# Cpcis_connectors_P1_P6.net
KiCad netlist of a schematic drawn in Altium Designer
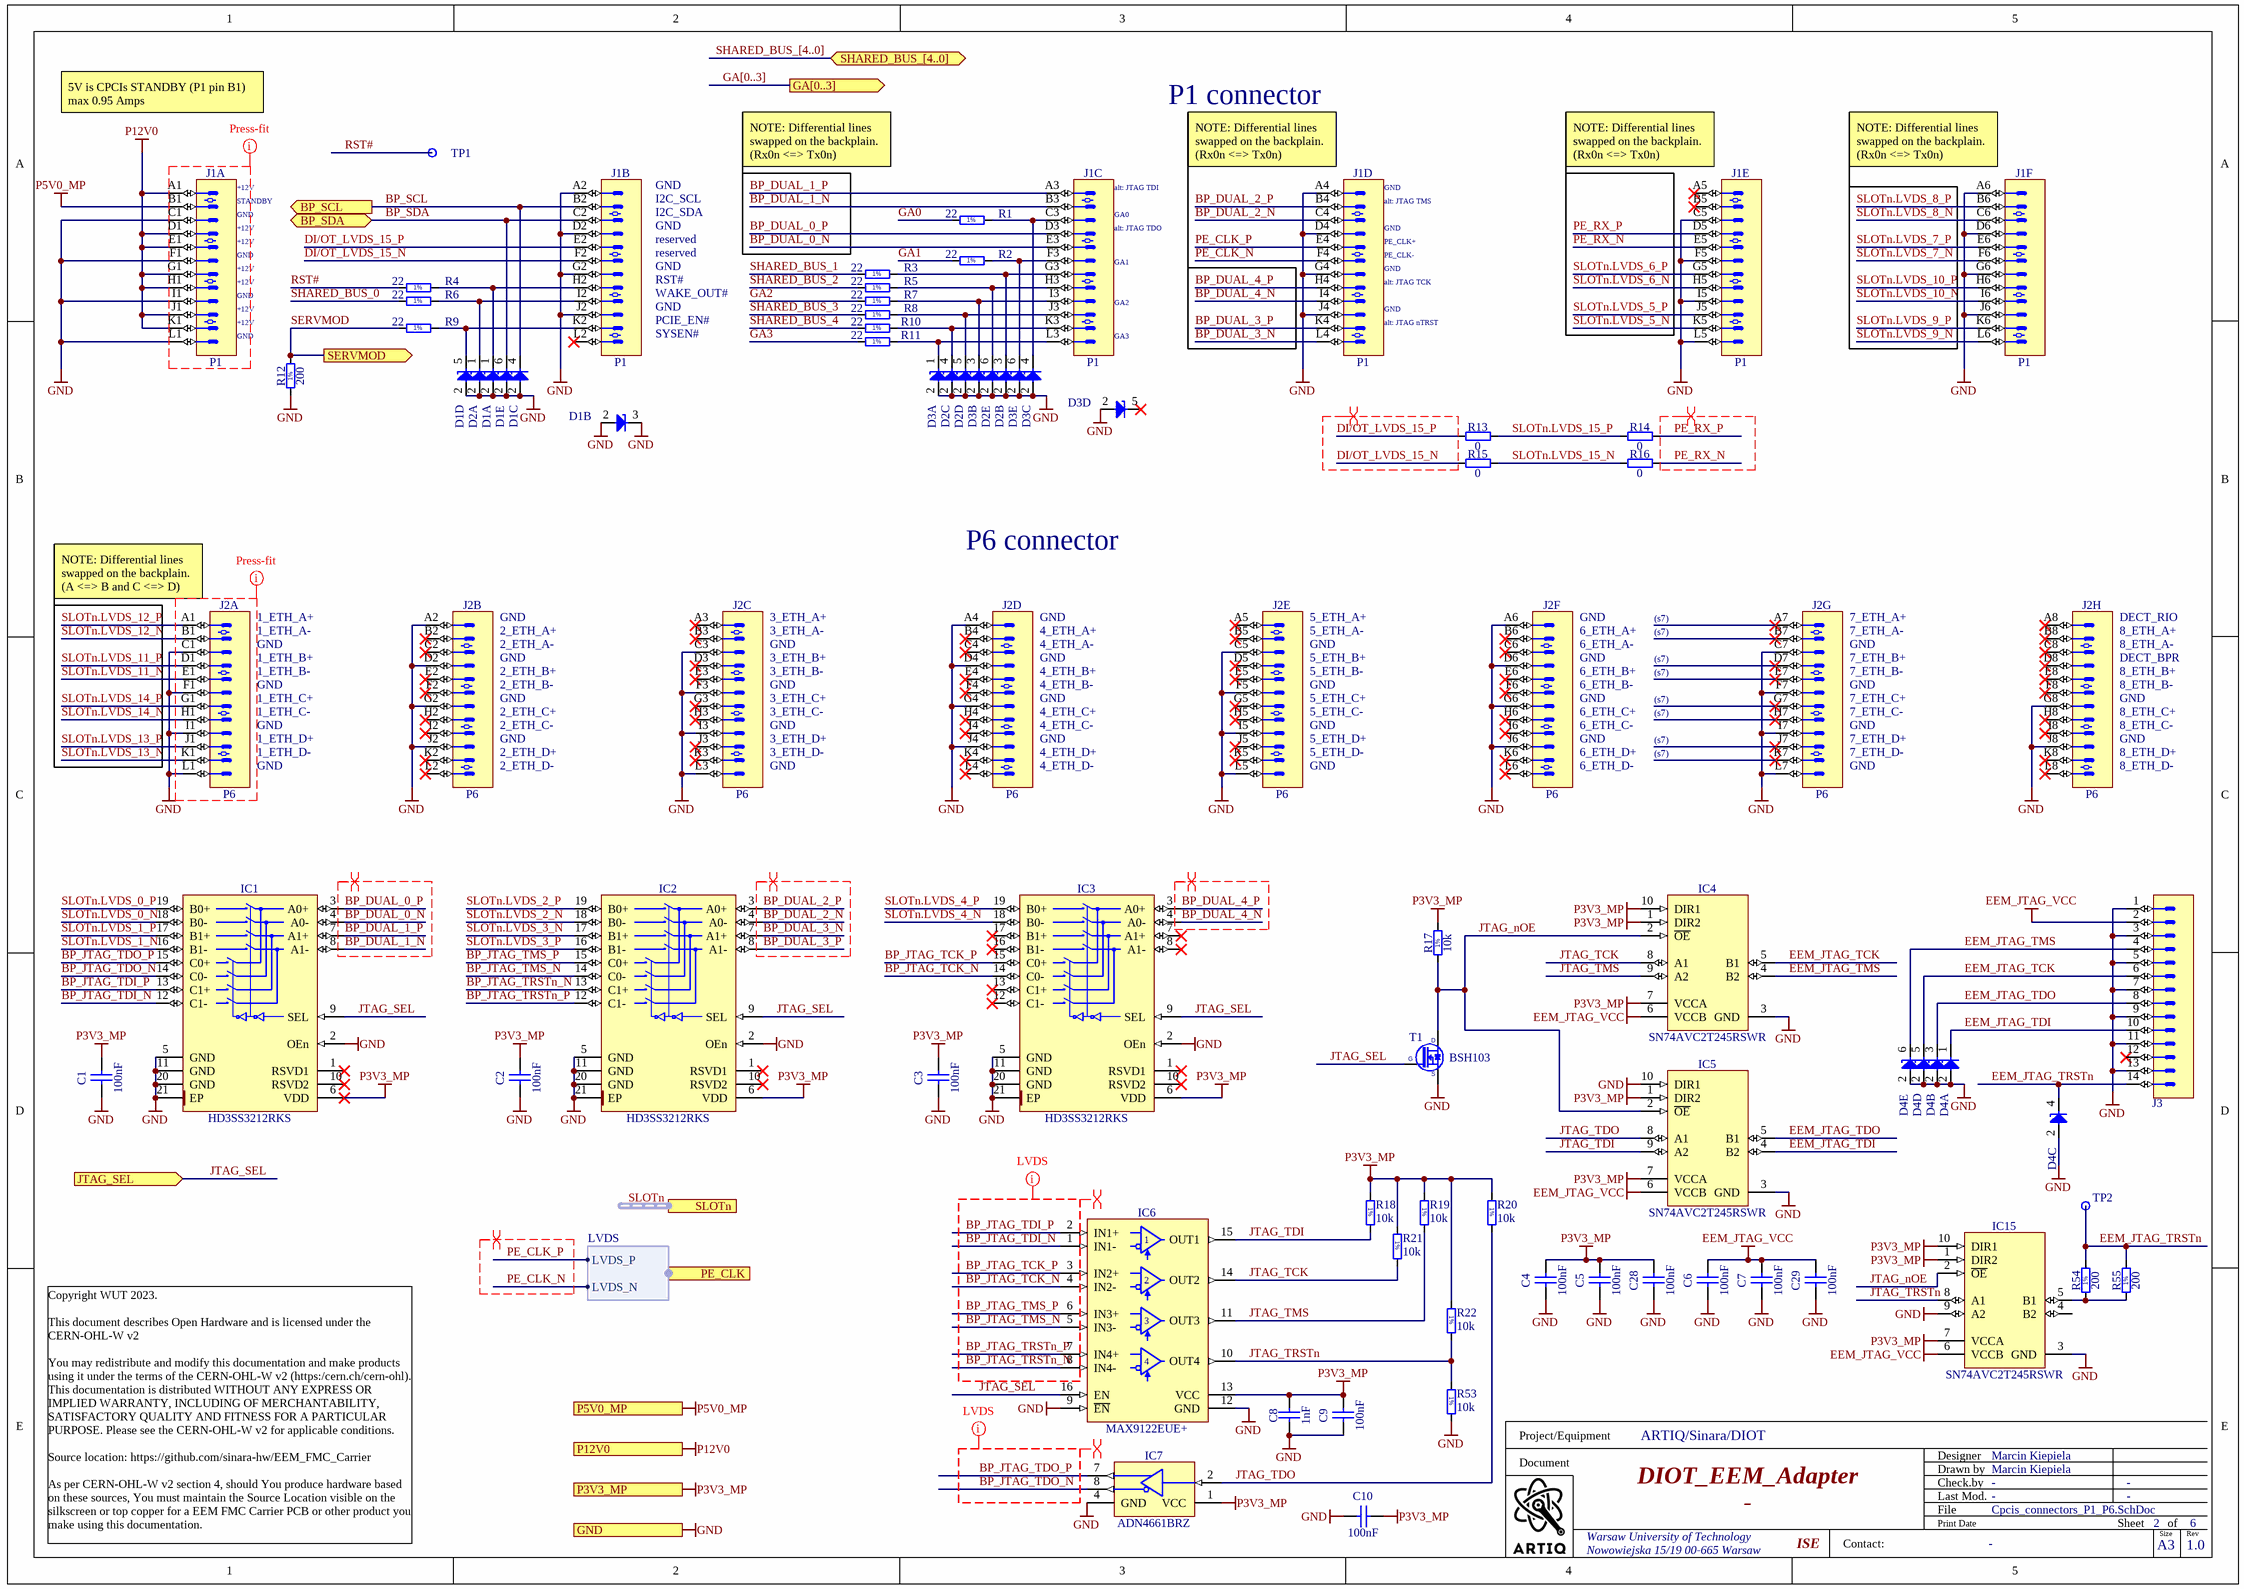
[diagram p0: Cpcis_connectors_P1_P6.SchDoc]

(export (version "E")
  (design (tool "Eeschema 10.0.6"))
  (components
    (comp (ref "C1")
      (value "100nF")
      (footprint "CAPC1005X55N")
      (description "Non-polarised capacitor")
      (fields
        (field (name "PART NUMBER") "CC0402_100NF_16V_10%_X7R")
        (field (name "VOLTAGE") "16V")
        (field (name "AUTHOR") "CERN DEM JLC")
      )
      (libsource (lib "Capacitors") (part "Capacitor - non polarized"))
    )
    (comp (ref "C2")
      (value "100nF")
      (footprint "CAPC1005X55N")
      (description "Non-polarised capacitor")
      (fields
        (field (name "PART NUMBER") "CC0402_100NF_16V_10%_X7R")
        (field (name "VOLTAGE") "16V")
        (field (name "AUTHOR") "CERN DEM JLC")
      )
      (libsource (lib "Capacitors") (part "Capacitor - non polarized"))
    )
    (comp (ref "C3")
      (value "100nF")
      (footprint "CAPC1005X55N")
      (description "Non-polarised capacitor")
      (fields
        (field (name "PART NUMBER") "CC0402_100NF_16V_10%_X7R")
        (field (name "VOLTAGE") "16V")
        (field (name "AUTHOR") "CERN DEM JLC")
      )
      (libsource (lib "Capacitors") (part "Capacitor - non polarized"))
    )
    (comp (ref "C4")
      (value "100nF")
      (footprint "CAPC1005X55N")
      (description "Non-polarised capacitor")
      (fields
        (field (name "PART NUMBER") "CC0402_100NF_16V_10%_X7R")
        (field (name "VOLTAGE") "16V")
        (field (name "AUTHOR") "CERN DEM JLC")
      )
      (libsource (lib "Capacitors") (part "Capacitor - non polarized"))
    )
    (comp (ref "C5")
      (value "100nF")
      (footprint "CAPC1005X55N")
      (description "Non-polarised capacitor")
      (fields
        (field (name "PART NUMBER") "CC0402_100NF_16V_10%_X7R")
        (field (name "VOLTAGE") "16V")
        (field (name "AUTHOR") "CERN DEM JLC")
      )
      (libsource (lib "Capacitors") (part "Capacitor - non polarized"))
    )
    (comp (ref "C6")
      (value "100nF")
      (footprint "CAPC1005X55N")
      (description "Non-polarised capacitor")
      (fields
        (field (name "PART NUMBER") "CC0402_100NF_16V_10%_X7R")
        (field (name "VOLTAGE") "16V")
        (field (name "AUTHOR") "CERN DEM JLC")
      )
      (libsource (lib "Capacitors") (part "Capacitor - non polarized"))
    )
    (comp (ref "C7")
      (value "100nF")
      (footprint "CAPC1005X55N")
      (description "Non-polarised capacitor")
      (fields
        (field (name "PART NUMBER") "CC0402_100NF_16V_10%_X7R")
        (field (name "VOLTAGE") "16V")
        (field (name "AUTHOR") "CERN DEM JLC")
      )
      (libsource (lib "Capacitors") (part "Capacitor - non polarized"))
    )
    (comp (ref "C8")
      (value "1nF")
      (footprint "CAPC1005X55N")
      (description "Non-polarised capacitor")
      (fields
        (field (name "MANUFACTURER PART NUMBER") "CC0402_1NF_50V_10%_X7R")
        (field (name "MANUFACTURER") "GENERIC")
        (field (name "AUTHOR") "CERN DEM JLC")
      )
      (libsource (lib "Capacitors") (part "Capacitor - non polarized"))
    )
    (comp (ref "C9")
      (value "100nF")
      (footprint "CAPC1005X55N")
      (description "Non-polarised capacitor")
      (fields
        (field (name "PART NUMBER") "CC0402_100NF_16V_10%_X7R")
        (field (name "VOLTAGE") "16V")
        (field (name "AUTHOR") "CERN DEM JLC")
      )
      (libsource (lib "Capacitors") (part "Capacitor - non polarized"))
    )
    (comp (ref "C10")
      (value "100nF")
      (footprint "CAPC1005X55N")
      (description "Non-polarised capacitor")
      (fields
        (field (name "PART NUMBER") "CC0402_100NF_16V_10%_X7R")
        (field (name "VOLTAGE") "16V")
        (field (name "AUTHOR") "CERN DEM JLC")
      )
      (libsource (lib "Capacitors") (part "Capacitor - non polarized"))
    )
    (comp (ref "C28")
      (value "100nF")
      (footprint "CAPC1005X55N")
      (description "Non-polarised capacitor")
      (fields
        (field (name "PART NUMBER") "CC0402_100NF_16V_10%_X7R")
        (field (name "VOLTAGE") "16V")
        (field (name "AUTHOR") "CERN DEM JLC")
      )
      (libsource (lib "Capacitors") (part "Capacitor - non polarized"))
    )
    (comp (ref "C29")
      (value "100nF")
      (footprint "CAPC1005X55N")
      (description "Non-polarised capacitor")
      (fields
        (field (name "PART NUMBER") "CC0402_100NF_16V_10%_X7R")
        (field (name "VOLTAGE") "16V")
        (field (name "AUTHOR") "CERN DEM JLC")
      )
      (libsource (lib "Capacitors") (part "Capacitor - non polarized"))
    )
    (comp (ref "D1")
      (value "PESD3V3L5UY")
      (footprint "SOT65P210X110-6N")
      (description "Fivefold ESD Protection Diode Arrays")
      (fields
        (field (name "VOLTAGE") "3.3V")
        (field (name "POWER") "200W")
        (field (name "AUTHOR") "CERN DEM WB")
      )
      (libsource (lib "ICs And Semiconductors") (part "PESD Array 5diodes 6pins Common anode2"))
    )
    (comp (ref "D2")
      (value "PESD3V3L5UY")
      (footprint "SOT65P210X110-6N")
      (description "Fivefold ESD Protection Diode Arrays")
      (fields
        (field (name "VOLTAGE") "3.3V")
        (field (name "POWER") "200W")
        (field (name "AUTHOR") "CERN DEM WB")
      )
      (libsource (lib "ICs And Semiconductors") (part "PESD Array 5diodes 6pins Common anode2"))
    )
    (comp (ref "D3")
      (value "PESD3V3L5UY")
      (footprint "SOT65P210X110-6N")
      (description "Fivefold ESD Protection Diode Arrays")
      (fields
        (field (name "VOLTAGE") "3.3V")
        (field (name "POWER") "200W")
        (field (name "AUTHOR") "CERN DEM WB")
      )
      (libsource (lib "ICs And Semiconductors") (part "PESD Array 5diodes 6pins Common anode2"))
    )
    (comp (ref "D4")
      (value "PESD3V3L5UY")
      (footprint "SOT65P210X110-6N")
      (description "Fivefold ESD Protection Diode Arrays")
      (fields
        (field (name "VOLTAGE") "3.3V")
        (field (name "POWER") "200W")
        (field (name "AUTHOR") "CERN DEM WB")
      )
      (libsource (lib "ICs And Semiconductors") (part "PESD Array 5diodes 6pins Common anode2"))
    )
    (comp (ref "IC1")
      (value "HD3SS3212RKS")
      (footprint "TEXAS_RKS0020A")
      (description "Two-Channel Differential 2:1/1:2 USB3.1 Mux/Demux")
      (fields (field (name "MANUFACTURER") "TEXAS INSTRUMENTS") (field (name "AUTHOR") "CERN DEM BC"))
      (libsource (lib "ICs And Semiconductors") (part "HD3SS3212RKS"))
    )
    (comp (ref "IC2")
      (value "HD3SS3212RKS")
      (footprint "TEXAS_RKS0020A")
      (description "Two-Channel Differential 2:1/1:2 USB3.1 Mux/Demux")
      (fields (field (name "MANUFACTURER") "TEXAS INSTRUMENTS") (field (name "AUTHOR") "CERN DEM BC"))
      (libsource (lib "ICs And Semiconductors") (part "HD3SS3212RKS"))
    )
    (comp (ref "IC3")
      (value "HD3SS3212RKS")
      (footprint "TEXAS_RKS0020A")
      (description "Two-Channel Differential 2:1/1:2 USB3.1 Mux/Demux")
      (fields (field (name "MANUFACTURER") "TEXAS INSTRUMENTS") (field (name "AUTHOR") "CERN DEM BC"))
      (libsource (lib "ICs And Semiconductors") (part "HD3SS3212RKS"))
    )
    (comp (ref "IC4")
      (value "SN74AVC2T245RSWR")
      (footprint "QFN40P140X180X55-10N")
      (description "Dual-Bit Dual-Supply Bus Transceiver With Configurable Voltage Translation and 3-State Outputs")
      (fields (field (name "MANUFACTURER") "TEXAS INSTRUMENTS") (field (name "AUTHOR") "CERN DEM JLC"))
      (libsource (lib "ICs And Semiconductors") (part "742T245"))
    )
    (comp (ref "IC5")
      (value "SN74AVC2T245RSWR")
      (footprint "QFN40P140X180X55-10N")
      (description "Dual-Bit Dual-Supply Bus Transceiver With Configurable Voltage Translation and 3-State Outputs")
      (fields (field (name "MANUFACTURER") "TEXAS INSTRUMENTS") (field (name "AUTHOR") "CERN DEM JLC"))
      (libsource (lib "ICs And Semiconductors") (part "742T245"))
    )
    (comp (ref "IC6")
      (value "MAX9122EUE+")
      (footprint "SOP65P640X110-16N")
      (description "Quad LVDS Line Receivers with Integrated Termination and Flow-Through Pinout")
      (fields (field (name "MANUFACTURER") "MAXIM") (field (name "AUTHOR") "CERN DEM MR"))
      (libsource (lib "ICs And Semiconductors") (part "MAX9122"))
    )
    (comp (ref "IC7")
      (value "ADN4661BRZ")
      (footprint "SOIC127P600X175-8N")
      (description "Single, 3V, CMOS, LVDS, High Speed Differential Driver")
      (fields (field (name "MANUFACTURER") "ANALOG DEVICES") (field (name "AUTHOR") "CERN DEM JMW"))
      (libsource (lib "ICs And Semiconductors") (part "ADN4661"))
    )
    (comp (ref "IC15")
      (value "SN74AVC2T245RSWR")
      (footprint "QFN40P140X180X55-10N")
      (description "Dual-Bit Dual-Supply Bus Transceiver With Configurable Voltage Translation and 3-State Outputs")
      (fields (field (name "MANUFACTURER") "TEXAS INSTRUMENTS") (field (name "AUTHOR") "CERN DEM JLC"))
      (libsource (lib "ICs And Semiconductors") (part "742T245"))
    )
    (comp (ref "J1")
      (value "P1")
      (footprint "AMPHENOL_10052825-101LF")
      (description "72 Contacts Header, 6 Columns, 4 Pairs per Column")
      (fields
        (field (name "PART NUMBER") "AMPHENOL_10052825-101LF")
        (field (name "MANUFACTURER") "AMPHENOL")
        (field (name "AUTHOR") "CERN DEM MR")
      )
      (libsource (lib "Connectors") (part "AMPHENOL_10052825-101LF"))
    )
    (comp (ref "J2")
      (value "P6")
      (footprint "AMPHENOL_10052838-101LF")
      (description "96 Contacts Header, 8 Columns, 4 Pairs per Column")
      (fields
        (field (name "PART NUMBER") "AMPHENOL_10052838-101LF")
        (field (name "MANUFACTURER") "AMPHENOL")
        (field (name "AUTHOR") "CERN DEM MR")
      )
      (libsource (lib "Connectors") (part "AMPHENOL_10052838-101LF"))
    )
    (comp (ref "J3")
      (value "Milli-Grid™")
      (footprint "MOLEX_87832-1420")
      (description "Connector 14 Male")
      (fields
        (field (name "PART NUMBER") "MOLEX_87832-1420")
        (field (name "MANUFACTURER") "MOLEX")
        (field (name "AUTHOR") "CERN DEM JLC")
      )
      (libsource (lib "Connectors") (part "Connector 14 Male"))
    )
    (comp (ref "R1")
      (value "22")
      (footprint "RESC1005X40N")
      (description "Resistor - 1%")
      (fields
        (field (name "PART NUMBER") "R0402_22R_1%_0.0625W_100PPM")
        (field (name "POWER") "0.0625W")
        (field (name "AUTHOR") "CERN DEM JLC")
      )
      (libsource (lib "Resistors") (part "Resistor - 1%"))
    )
    (comp (ref "R2")
      (value "22")
      (footprint "RESC1005X40N")
      (description "Resistor - 1%")
      (fields
        (field (name "PART NUMBER") "R0402_22R_1%_0.0625W_100PPM")
        (field (name "POWER") "0.0625W")
        (field (name "AUTHOR") "CERN DEM JLC")
      )
      (libsource (lib "Resistors") (part "Resistor - 1%"))
    )
    (comp (ref "R3")
      (value "22")
      (footprint "RESC1005X40N")
      (description "Resistor - 1%")
      (fields
        (field (name "PART NUMBER") "R0402_22R_1%_0.0625W_100PPM")
        (field (name "POWER") "0.0625W")
        (field (name "AUTHOR") "CERN DEM JLC")
      )
      (libsource (lib "Resistors") (part "Resistor - 1%"))
    )
    (comp (ref "R4")
      (value "22")
      (footprint "RESC1005X40N")
      (description "Resistor - 1%")
      (fields
        (field (name "PART NUMBER") "R0402_22R_1%_0.0625W_100PPM")
        (field (name "POWER") "0.0625W")
        (field (name "AUTHOR") "CERN DEM JLC")
      )
      (libsource (lib "Resistors") (part "Resistor - 1%"))
    )
    (comp (ref "R5")
      (value "22")
      (footprint "RESC1005X40N")
      (description "Resistor - 1%")
      (fields
        (field (name "PART NUMBER") "R0402_22R_1%_0.0625W_100PPM")
        (field (name "POWER") "0.0625W")
        (field (name "AUTHOR") "CERN DEM JLC")
      )
      (libsource (lib "Resistors") (part "Resistor - 1%"))
    )
    (comp (ref "R6")
      (value "22")
      (footprint "RESC1005X40N")
      (description "Resistor - 1%")
      (fields
        (field (name "PART NUMBER") "R0402_22R_1%_0.0625W_100PPM")
        (field (name "POWER") "0.0625W")
        (field (name "AUTHOR") "CERN DEM JLC")
      )
      (libsource (lib "Resistors") (part "Resistor - 1%"))
    )
    (comp (ref "R7")
      (value "22")
      (footprint "RESC1005X40N")
      (description "Resistor - 1%")
      (fields
        (field (name "PART NUMBER") "R0402_22R_1%_0.0625W_100PPM")
        (field (name "POWER") "0.0625W")
        (field (name "AUTHOR") "CERN DEM JLC")
      )
      (libsource (lib "Resistors") (part "Resistor - 1%"))
    )
    (comp (ref "R8")
      (value "22")
      (footprint "RESC1005X40N")
      (description "Resistor - 1%")
      (fields
        (field (name "PART NUMBER") "R0402_22R_1%_0.0625W_100PPM")
        (field (name "POWER") "0.0625W")
        (field (name "AUTHOR") "CERN DEM JLC")
      )
      (libsource (lib "Resistors") (part "Resistor - 1%"))
    )
    (comp (ref "R9")
      (value "22")
      (footprint "RESC1005X40N")
      (description "Resistor - 1%")
      (fields
        (field (name "PART NUMBER") "R0402_22R_1%_0.0625W_100PPM")
        (field (name "POWER") "0.0625W")
        (field (name "AUTHOR") "CERN DEM JLC")
      )
      (libsource (lib "Resistors") (part "Resistor - 1%"))
    )
    (comp (ref "R10")
      (value "22")
      (footprint "RESC1005X40N")
      (description "Resistor - 1%")
      (fields
        (field (name "PART NUMBER") "R0402_22R_1%_0.0625W_100PPM")
        (field (name "POWER") "0.0625W")
        (field (name "AUTHOR") "CERN DEM JLC")
      )
      (libsource (lib "Resistors") (part "Resistor - 1%"))
    )
    (comp (ref "R11")
      (value "22")
      (footprint "RESC1005X40N")
      (description "Resistor - 1%")
      (fields
        (field (name "PART NUMBER") "R0402_22R_1%_0.0625W_100PPM")
        (field (name "POWER") "0.0625W")
        (field (name "AUTHOR") "CERN DEM JLC")
      )
      (libsource (lib "Resistors") (part "Resistor - 1%"))
    )
    (comp (ref "R12")
      (value "200")
      (footprint "RESC1005X40N")
      (description "Resistor - 1%")
      (fields
        (field (name "PART NUMBER") "R0402_200R_1%_0.0625W_100PPM")
        (field (name "POWER") "0.0625W")
        (field (name "AUTHOR") "CERN DEM JLC")
      )
      (libsource (lib "Resistors") (part "Resistor - 1%"))
    )
    (comp (ref "R13")
      (value "0")
      (footprint "RESC0603X28N")
      (description "Resistor")
      (fields
        (field (name "PART NUMBER") "R0201_0R_JUMPER")
        (field (name "MANUFACTURER") "GENERIC")
        (field (name "AUTHOR") "CERN DEM JLC")
      )
      (libsource (lib "Resistors") (part "Resistor"))
    )
    (comp (ref "R14")
      (value "0")
      (footprint "RESC0603X28N")
      (description "Resistor")
      (fields
        (field (name "PART NUMBER") "R0201_0R_JUMPER")
        (field (name "MANUFACTURER") "GENERIC")
        (field (name "AUTHOR") "CERN DEM JLC")
      )
      (libsource (lib "Resistors") (part "Resistor"))
    )
    (comp (ref "R15")
      (value "0")
      (footprint "RESC0603X28N")
      (description "Resistor")
      (fields
        (field (name "PART NUMBER") "R0201_0R_JUMPER")
        (field (name "MANUFACTURER") "GENERIC")
        (field (name "AUTHOR") "CERN DEM JLC")
      )
      (libsource (lib "Resistors") (part "Resistor"))
    )
    (comp (ref "R16")
      (value "0")
      (footprint "RESC0603X28N")
      (description "Resistor")
      (fields
        (field (name "PART NUMBER") "R0201_0R_JUMPER")
        (field (name "MANUFACTURER") "GENERIC")
        (field (name "AUTHOR") "CERN DEM JLC")
      )
      (libsource (lib "Resistors") (part "Resistor"))
    )
    (comp (ref "R17")
      (value "10k")
      (footprint "RESC1005X40N")
      (description "Resistor - 1%")
      (fields
        (field (name "PART NUMBER") "R0402_10K_1%_0.0625W_100PPM")
        (field (name "POWER") "0.0625W")
        (field (name "AUTHOR") "CERN DEM JLC")
      )
      (libsource (lib "Resistors") (part "Resistor - 1%"))
    )
    (comp (ref "R18")
      (value "10k")
      (footprint "RESC1005X40N")
      (description "Resistor - 1%")
      (fields
        (field (name "PART NUMBER") "R0402_10K_1%_0.0625W_100PPM")
        (field (name "POWER") "0.0625W")
        (field (name "AUTHOR") "CERN DEM JLC")
      )
      (libsource (lib "Resistors") (part "Resistor - 1%"))
    )
    (comp (ref "R19")
      (value "10k")
      (footprint "RESC1005X40N")
      (description "Resistor - 1%")
      (fields
        (field (name "PART NUMBER") "R0402_10K_1%_0.0625W_100PPM")
        (field (name "POWER") "0.0625W")
        (field (name "AUTHOR") "CERN DEM JLC")
      )
      (libsource (lib "Resistors") (part "Resistor - 1%"))
    )
    (comp (ref "R20")
      (value "10k")
      (footprint "RESC1005X40N")
      (description "Resistor - 1%")
      (fields
        (field (name "PART NUMBER") "R0402_10K_1%_0.0625W_100PPM")
        (field (name "POWER") "0.0625W")
        (field (name "AUTHOR") "CERN DEM JLC")
      )
      (libsource (lib "Resistors") (part "Resistor - 1%"))
    )
    (comp (ref "R21")
      (value "10k")
      (footprint "RESC1005X40N")
      (description "Resistor - 1%")
      (fields
        (field (name "PART NUMBER") "R0402_10K_1%_0.0625W_100PPM")
        (field (name "POWER") "0.0625W")
        (field (name "AUTHOR") "CERN DEM JLC")
      )
      (libsource (lib "Resistors") (part "Resistor - 1%"))
    )
    (comp (ref "R22")
      (value "10k")
      (footprint "RESC1005X40N")
      (description "Resistor - 1%")
      (fields
        (field (name "PART NUMBER") "R0402_10K_1%_0.0625W_100PPM")
        (field (name "POWER") "0.0625W")
        (field (name "AUTHOR") "CERN DEM JLC")
      )
      (libsource (lib "Resistors") (part "Resistor - 1%"))
    )
    (comp (ref "R53")
      (value "10k")
      (footprint "RESC1005X40N")
      (description "Resistor - 1%")
      (fields
        (field (name "PART NUMBER") "R0402_10K_1%_0.0625W_100PPM")
        (field (name "POWER") "0.0625W")
        (field (name "AUTHOR") "CERN DEM JLC")
      )
      (libsource (lib "Resistors") (part "Resistor - 1%"))
    )
    (comp (ref "R54")
      (value "200")
      (footprint "RESC1005X40N")
      (description "Resistor - 1%")
      (fields
        (field (name "PART NUMBER") "R0402_200R_1%_0.0625W_100PPM")
        (field (name "POWER") "0.0625W")
        (field (name "AUTHOR") "CERN DEM JLC")
      )
      (libsource (lib "Resistors") (part "Resistor - 1%"))
    )
    (comp (ref "R55")
      (value "200")
      (footprint "RESC1005X40N")
      (description "Resistor - 1%")
      (fields
        (field (name "PART NUMBER") "R0402_200R_1%_0.0625W_100PPM")
        (field (name "POWER") "0.0625W")
        (field (name "AUTHOR") "CERN DEM JLC")
      )
      (libsource (lib "Resistors") (part "Resistor - 1%"))
    )
    (comp (ref "T1")
      (value "BSH103")
      (footprint "SOT95P230X110-3N")
      (description "N-CHANNEL MOSFET WITH DIODE")
      (fields (field (name "MANUFACTURER") "NEXPERIA") (field (name "AUTHOR") "CERN DEM JLC"))
      (libsource (lib "ICs And Semiconductors") (part "N-MOSFET-D 1G 2S 3D"))
    )
    (comp (ref "TP1")
      (value "Test Point")
      (footprint "TPS127")
      (fields (field (name "PART NUMBER") "SMD_PAD_1.27X1.27MM") (field (name "AUTHOR") "CERN DEM JLC"))
      (libsource (lib "Eletro-mechanical") (part "Test Point"))
    )
    (comp (ref "TP2")
      (value "Test Point")
      (footprint "TPS127")
      (fields (field (name "PART NUMBER") "SMD_PAD_1.27X1.27MM") (field (name "AUTHOR") "CERN DEM JLC"))
      (libsource (lib "Eletro-mechanical") (part "Test Point"))
    )
  )
  (nets
    (net (code "3") (name "/BP_DUAL_0_N") (class "Default")
      (node (ref "IC1") (pin "4") (pinfunction "A0-_4") (pintype "bidirectional"))
      (node (ref "J1") (pin "E3") (pinfunction "E3_E3") (pintype "bidirectional"))
    )
    (net (code "4") (name "/BP_DUAL_0_P") (class "Default")
      (node (ref "IC1") (pin "3") (pinfunction "A0+_3") (pintype "bidirectional"))
      (node (ref "J1") (pin "D3") (pinfunction "D3_D3") (pintype "bidirectional"))
    )
    (net (code "5") (name "/BP_DUAL_1_N") (class "Default")
      (node (ref "IC1") (pin "8") (pinfunction "A1-_8") (pintype "bidirectional"))
      (node (ref "J1") (pin "B3") (pinfunction "B3_B3") (pintype "bidirectional"))
    )
    (net (code "6") (name "/BP_DUAL_1_P") (class "Default")
      (node (ref "IC1") (pin "7") (pinfunction "A1+_7") (pintype "bidirectional"))
      (node (ref "J1") (pin "A3") (pinfunction "A3_A3") (pintype "bidirectional"))
    )
    (net (code "7") (name "/BP_DUAL_2_N") (class "Default")
      (node (ref "IC2") (pin "4") (pinfunction "A0-_4") (pintype "bidirectional"))
      (node (ref "J1") (pin "C4") (pinfunction "C4_C4") (pintype "bidirectional"))
    )
    (net (code "8") (name "/BP_DUAL_2_P") (class "Default")
      (node (ref "IC2") (pin "3") (pinfunction "A0+_3") (pintype "bidirectional"))
      (node (ref "J1") (pin "B4") (pinfunction "B4_B4") (pintype "bidirectional"))
    )
    (net (code "9") (name "/BP_DUAL_3_N") (class "Default")
      (node (ref "IC2") (pin "7") (pinfunction "A1+_7") (pintype "bidirectional"))
      (node (ref "J1") (pin "L4") (pinfunction "L4_L4") (pintype "bidirectional"))
    )
    (net (code "10") (name "/BP_DUAL_3_P") (class "Default")
      (node (ref "IC2") (pin "8") (pinfunction "A1-_8") (pintype "bidirectional"))
      (node (ref "J1") (pin "K4") (pinfunction "K4_K4") (pintype "bidirectional"))
    )
    (net (code "11") (name "/BP_DUAL_4_N") (class "Default")
      (node (ref "IC3") (pin "4") (pinfunction "A0-_4") (pintype "bidirectional"))
      (node (ref "J1") (pin "I4") (pinfunction "I4_I4") (pintype "bidirectional"))
    )
    (net (code "12") (name "/BP_DUAL_4_P") (class "Default")
      (node (ref "IC3") (pin "3") (pinfunction "A0+_3") (pintype "bidirectional"))
      (node (ref "J1") (pin "H4") (pinfunction "H4_H4") (pintype "bidirectional"))
    )
    (net (code "13") (name "/BP_JTAG_TCK_N") (class "Default")
      (node (ref "IC3") (pin "14") (pinfunction "C0-_14") (pintype "bidirectional"))
      (node (ref "IC6") (pin "4") (pinfunction "IN2-_4") (pintype "input"))
    )
    (net (code "14") (name "/BP_JTAG_TCK_P") (class "Default")
      (node (ref "IC3") (pin "15") (pinfunction "C0+_15") (pintype "bidirectional"))
      (node (ref "IC6") (pin "3") (pinfunction "IN2+_3") (pintype "input"))
    )
    (net (code "15") (name "/BP_JTAG_TDI_N") (class "Default")
      (node (ref "IC1") (pin "12") (pinfunction "C1-_12") (pintype "bidirectional"))
      (node (ref "IC6") (pin "1") (pinfunction "IN1-_1") (pintype "input"))
    )
    (net (code "16") (name "/BP_JTAG_TDI_P") (class "Default")
      (node (ref "IC1") (pin "13") (pinfunction "C1+_13") (pintype "bidirectional"))
      (node (ref "IC6") (pin "2") (pinfunction "IN1+_2") (pintype "input"))
    )
    (net (code "17") (name "/BP_JTAG_TDO_N") (class "Default")
      (node (ref "IC1") (pin "14") (pinfunction "C0-_14") (pintype "bidirectional"))
      (node (ref "IC7") (pin "8") (pinfunction "DOUT-_8") (pintype "output"))
    )
    (net (code "18") (name "/BP_JTAG_TDO_P") (class "Default")
      (node (ref "IC1") (pin "15") (pinfunction "C0+_15") (pintype "bidirectional"))
      (node (ref "IC7") (pin "7") (pinfunction "DOUT+_7") (pintype "output"))
    )
    (net (code "19") (name "/BP_JTAG_TMS_N") (class "Default")
      (node (ref "IC2") (pin "14") (pinfunction "C0-_14") (pintype "bidirectional"))
      (node (ref "IC6") (pin "5") (pinfunction "IN3-_5") (pintype "input"))
    )
    (net (code "20") (name "/BP_JTAG_TMS_P") (class "Default")
      (node (ref "IC2") (pin "15") (pinfunction "C0+_15") (pintype "bidirectional"))
      (node (ref "IC6") (pin "6") (pinfunction "IN3+_6") (pintype "input"))
    )
    (net (code "21") (name "/BP_JTAG_TRSTn_N") (class "Default")
      (node (ref "IC2") (pin "13") (pinfunction "C1+_13") (pintype "bidirectional"))
      (node (ref "IC6") (pin "8") (pinfunction "IN4-_8") (pintype "input"))
    )
    (net (code "22") (name "/BP_JTAG_TRSTn_P") (class "Default")
      (node (ref "IC2") (pin "12") (pinfunction "C1-_12") (pintype "bidirectional"))
      (node (ref "IC6") (pin "7") (pinfunction "IN4+_7") (pintype "input"))
    )
    (net (code "23") (name "/BP_SCL") (class "Default")
      (node (ref "D1") (pin "4") (pinfunction "C_4") (pintype "passive"))
      (node (ref "J1") (pin "B2") (pinfunction "B2_B2") (pintype "bidirectional"))
    )
    (net (code "24") (name "/BP_SDA") (class "Default")
      (node (ref "D1") (pin "6") (pinfunction "C_6") (pintype "passive"))
      (node (ref "J1") (pin "C2") (pinfunction "C2_C2") (pintype "bidirectional"))
    )
    (net (code "25") (name "/DI{slash}OT_LVDS_15_N") (class "Default")
      (node (ref "J1") (pin "F2") (pinfunction "F2_F2") (pintype "bidirectional"))
      (node (ref "R15") (pin "1") (pinfunction "1_1") (pintype "passive"))
    )
    (net (code "26") (name "/DI{slash}OT_LVDS_15_P") (class "Default")
      (node (ref "J1") (pin "E2") (pinfunction "E2_E2") (pintype "bidirectional"))
      (node (ref "R13") (pin "1") (pinfunction "1_1") (pintype "passive"))
    )
    (net (code "27") (name "/EEM_JTAG_TCK") (class "Default")
      (node (ref "D4") (pin "5") (pinfunction "C_5") (pintype "passive"))
      (node (ref "IC4") (pin "5") (pinfunction "B1_5") (pintype "bidirectional"))
      (node (ref "J3") (pin "6") (pinfunction "6_6") (pintype "bidirectional"))
    )
    (net (code "28") (name "/EEM_JTAG_TDI") (class "Default")
      (node (ref "D4") (pin "1") (pinfunction "C_1") (pintype "passive"))
      (node (ref "IC5") (pin "4") (pinfunction "B2_4") (pintype "bidirectional"))
      (node (ref "J3") (pin "10") (pinfunction "10_10") (pintype "bidirectional"))
    )
    (net (code "29") (name "/EEM_JTAG_TDO") (class "Default")
      (node (ref "D4") (pin "3") (pinfunction "C_3") (pintype "passive"))
      (node (ref "IC5") (pin "5") (pinfunction "B1_5") (pintype "bidirectional"))
      (node (ref "J3") (pin "8") (pinfunction "8_8") (pintype "bidirectional"))
    )
    (net (code "30") (name "/EEM_JTAG_TMS") (class "Default")
      (node (ref "D4") (pin "6") (pinfunction "C_6") (pintype "passive"))
      (node (ref "IC4") (pin "4") (pinfunction "B2_4") (pintype "bidirectional"))
      (node (ref "J3") (pin "4") (pinfunction "4_4") (pintype "bidirectional"))
    )
    (net (code "31") (name "/EEM_JTAG_TRSTn") (class "Default")
      (node (ref "D4") (pin "4") (pinfunction "C_4") (pintype "passive"))
      (node (ref "J3") (pin "14") (pinfunction "14_14") (pintype "bidirectional"))
      (node (ref "R54") (pin "2") (pinfunction "2_2") (pintype "passive"))
      (node (ref "R55") (pin "2") (pinfunction "2_2") (pintype "passive"))
      (node (ref "TP2") (pin "1") (pinfunction "1_1") (pintype "bidirectional"))
    )
    (net (code "32") (name "/GA0") (class "Default")
      (node (ref "R1") (pin "1") (pinfunction "1_1") (pintype "passive"))
    )
    (net (code "33") (name "/GA1") (class "Default")
      (node (ref "R2") (pin "1") (pinfunction "1_1") (pintype "passive"))
    )
    (net (code "34") (name "/GA2") (class "Default")
      (node (ref "R7") (pin "1") (pinfunction "1_1") (pintype "passive"))
    )
    (net (code "35") (name "/GA3") (class "Default")
      (node (ref "R11") (pin "1") (pinfunction "1_1") (pintype "passive"))
    )
    (net (code "37") (name "/JTAG_SEL") (class "Default")
      (node (ref "IC1") (pin "9") (pinfunction "SEL_9") (pintype "input"))
      (node (ref "IC2") (pin "9") (pinfunction "SEL_9") (pintype "input"))
      (node (ref "IC3") (pin "9") (pinfunction "SEL_9") (pintype "input"))
      (node (ref "IC6") (pin "16") (pinfunction "EN_16") (pintype "input"))
      (node (ref "T1") (pin "1") (pinfunction "G_1") (pintype "passive"))
    )
    (net (code "38") (name "/JTAG_TCK") (class "Default")
      (node (ref "IC4") (pin "8") (pinfunction "A1_8") (pintype "bidirectional"))
      (node (ref "IC6") (pin "14") (pinfunction "OUT2_14") (pintype "output"))
      (node (ref "R21") (pin "1") (pinfunction "1_1") (pintype "passive"))
    )
    (net (code "39") (name "/JTAG_TDI") (class "Default")
      (node (ref "IC5") (pin "9") (pinfunction "A2_9") (pintype "bidirectional"))
      (node (ref "IC6") (pin "15") (pinfunction "OUT1_15") (pintype "output"))
      (node (ref "R18") (pin "1") (pinfunction "1_1") (pintype "passive"))
    )
    (net (code "40") (name "/JTAG_TDO") (class "Default")
      (node (ref "IC5") (pin "8") (pinfunction "A1_8") (pintype "bidirectional"))
      (node (ref "IC7") (pin "2") (pinfunction "DIN_2") (pintype "input"))
      (node (ref "R20") (pin "1") (pinfunction "1_1") (pintype "passive"))
    )
    (net (code "41") (name "/JTAG_TMS") (class "Default")
      (node (ref "IC4") (pin "9") (pinfunction "A2_9") (pintype "bidirectional"))
      (node (ref "IC6") (pin "11") (pinfunction "OUT3_11") (pintype "output"))
      (node (ref "R19") (pin "1") (pinfunction "1_1") (pintype "passive"))
    )
    (net (code "42") (name "/JTAG_TRSTn") (class "Default")
      (node (ref "IC15") (pin "8") (pinfunction "A1_8") (pintype "bidirectional"))
      (node (ref "IC6") (pin "10") (pinfunction "OUT4_10") (pintype "output"))
      (node (ref "R22") (pin "1") (pinfunction "1_1") (pintype "passive"))
      (node (ref "R53") (pin "2") (pinfunction "2_2") (pintype "passive"))
    )
    (net (code "43") (name "/JTAG_nOE") (class "Default")
      (node (ref "IC15") (pin "2") (pinfunction "~{OE}_2") (pintype "input"))
      (node (ref "IC4") (pin "2") (pinfunction "~{OE}_2") (pintype "input"))
      (node (ref "IC5") (pin "2") (pinfunction "~{OE}_2") (pintype "input"))
      (node (ref "R17") (pin "1") (pinfunction "1_1") (pintype "passive"))
      (node (ref "T1") (pin "3") (pinfunction "D_3") (pintype "passive"))
    )
    (net (code "44") (name "/PE_CLK_N") (class "Default")
      (node (ref "J1") (pin "F4") (pinfunction "F4_F4") (pintype "bidirectional"))
    )
    (net (code "45") (name "/PE_CLK_P") (class "Default")
      (node (ref "J1") (pin "E4") (pinfunction "E4_E4") (pintype "bidirectional"))
    )
    (net (code "46") (name "/PE_RX_N") (class "Default")
      (node (ref "J1") (pin "E5") (pinfunction "E5_E5") (pintype "bidirectional"))
      (node (ref "R16") (pin "2") (pinfunction "2_2") (pintype "passive"))
    )
    (net (code "47") (name "/PE_RX_P") (class "Default")
      (node (ref "J1") (pin "D5") (pinfunction "D5_D5") (pintype "bidirectional"))
      (node (ref "R14") (pin "2") (pinfunction "2_2") (pintype "passive"))
    )
    (net (code "48") (name "/RST#") (class "Default")
      (node (ref "R4") (pin "1") (pinfunction "1_1") (pintype "passive"))
      (node (ref "TP1") (pin "1") (pinfunction "1_1") (pintype "bidirectional"))
    )
    (net (code "49") (name "/SERVMOD") (class "Default")
      (node (ref "R12") (pin "2") (pinfunction "2_2") (pintype "passive"))
      (node (ref "R9") (pin "1") (pinfunction "1_1") (pintype "passive"))
    )
    (net (code "50") (name "/SHARED_BUS_0") (class "Default")
      (node (ref "R6") (pin "1") (pinfunction "1_1") (pintype "passive"))
    )
    (net (code "51") (name "/SHARED_BUS_1") (class "Default")
      (node (ref "R3") (pin "1") (pinfunction "1_1") (pintype "passive"))
    )
    (net (code "52") (name "/SHARED_BUS_2") (class "Default")
      (node (ref "R5") (pin "1") (pinfunction "1_1") (pintype "passive"))
    )
    (net (code "53") (name "/SHARED_BUS_3") (class "Default")
      (node (ref "R8") (pin "1") (pinfunction "1_1") (pintype "passive"))
    )
    (net (code "54") (name "/SHARED_BUS_4") (class "Default")
      (node (ref "R10") (pin "1") (pinfunction "1_1") (pintype "passive"))
    )
    (net (code "56") (name "/SLOTn.LVDS_0_N") (class "Default")
      (node (ref "IC1") (pin "18") (pinfunction "B0-_18") (pintype "bidirectional"))
    )
    (net (code "57") (name "/SLOTn.LVDS_0_P") (class "Default")
      (node (ref "IC1") (pin "19") (pinfunction "B0+_19") (pintype "bidirectional"))
    )
    (net (code "58") (name "/SLOTn.LVDS_1_N") (class "Default")
      (node (ref "IC1") (pin "16") (pinfunction "B1-_16") (pintype "bidirectional"))
    )
    (net (code "59") (name "/SLOTn.LVDS_1_P") (class "Default")
      (node (ref "IC1") (pin "17") (pinfunction "B1+_17") (pintype "bidirectional"))
    )
    (net (code "60") (name "/SLOTn.LVDS_2_N") (class "Default")
      (node (ref "IC2") (pin "18") (pinfunction "B0-_18") (pintype "bidirectional"))
    )
    (net (code "61") (name "/SLOTn.LVDS_2_P") (class "Default")
      (node (ref "IC2") (pin "19") (pinfunction "B0+_19") (pintype "bidirectional"))
    )
    (net (code "62") (name "/SLOTn.LVDS_3_N") (class "Default")
      (node (ref "IC2") (pin "17") (pinfunction "B1+_17") (pintype "bidirectional"))
    )
    (net (code "63") (name "/SLOTn.LVDS_3_P") (class "Default")
      (node (ref "IC2") (pin "16") (pinfunction "B1-_16") (pintype "bidirectional"))
    )
    (net (code "64") (name "/SLOTn.LVDS_4_N") (class "Default")
      (node (ref "IC3") (pin "18") (pinfunction "B0-_18") (pintype "bidirectional"))
    )
    (net (code "65") (name "/SLOTn.LVDS_4_P") (class "Default")
      (node (ref "IC3") (pin "19") (pinfunction "B0+_19") (pintype "bidirectional"))
    )
    (net (code "66") (name "/SLOTn.LVDS_5_N") (class "Default")
      (node (ref "J1") (pin "K5") (pinfunction "K5_K5") (pintype "bidirectional"))
    )
    (net (code "67") (name "/SLOTn.LVDS_5_P") (class "Default")
      (node (ref "J1") (pin "J5") (pinfunction "J5_J5") (pintype "bidirectional"))
    )
    (net (code "68") (name "/SLOTn.LVDS_6_N") (class "Default")
      (node (ref "J1") (pin "H5") (pinfunction "H5_H5") (pintype "bidirectional"))
    )
    (net (code "69") (name "/SLOTn.LVDS_6_P") (class "Default")
      (node (ref "J1") (pin "G5") (pinfunction "G5_G5") (pintype "bidirectional"))
    )
    (net (code "70") (name "/SLOTn.LVDS_7_N") (class "Default")
      (node (ref "J1") (pin "F6") (pinfunction "F6_F6") (pintype "bidirectional"))
    )
    (net (code "71") (name "/SLOTn.LVDS_7_P") (class "Default")
      (node (ref "J1") (pin "E6") (pinfunction "E6_E6") (pintype "bidirectional"))
    )
    (net (code "72") (name "/SLOTn.LVDS_8_N") (class "Default")
      (node (ref "J1") (pin "C6") (pinfunction "C6_C6") (pintype "bidirectional"))
    )
    (net (code "73") (name "/SLOTn.LVDS_8_P") (class "Default")
      (node (ref "J1") (pin "B6") (pinfunction "B6_B6") (pintype "bidirectional"))
    )
    (net (code "74") (name "/SLOTn.LVDS_9_N") (class "Default")
      (node (ref "J1") (pin "L6") (pinfunction "L6_L6") (pintype "bidirectional"))
    )
    (net (code "75") (name "/SLOTn.LVDS_9_P") (class "Default")
      (node (ref "J1") (pin "K6") (pinfunction "K6_K6") (pintype "bidirectional"))
    )
    (net (code "76") (name "/SLOTn.LVDS_10_N") (class "Default")
      (node (ref "J1") (pin "I6") (pinfunction "I6_I6") (pintype "bidirectional"))
    )
    (net (code "77") (name "/SLOTn.LVDS_10_P") (class "Default")
      (node (ref "J1") (pin "H6") (pinfunction "H6_H6") (pintype "bidirectional"))
    )
    (net (code "78") (name "/SLOTn.LVDS_11_N") (class "Default")
      (node (ref "J2") (pin "E1") (pinfunction "E1_E1") (pintype "bidirectional"))
    )
    (net (code "79") (name "/SLOTn.LVDS_11_P") (class "Default")
      (node (ref "J2") (pin "D1") (pinfunction "D1_D1") (pintype "bidirectional"))
    )
    (net (code "80") (name "/SLOTn.LVDS_12_N") (class "Default")
      (node (ref "J2") (pin "B1") (pinfunction "B1_B1") (pintype "bidirectional"))
    )
    (net (code "81") (name "/SLOTn.LVDS_12_P") (class "Default")
      (node (ref "J2") (pin "A1") (pinfunction "A1_A1") (pintype "bidirectional"))
    )
    (net (code "82") (name "/SLOTn.LVDS_13_N") (class "Default")
      (node (ref "J2") (pin "K1") (pinfunction "K1_K1") (pintype "bidirectional"))
    )
    (net (code "83") (name "/SLOTn.LVDS_13_P") (class "Default")
      (node (ref "J2") (pin "J1") (pinfunction "J1_J1") (pintype "bidirectional"))
    )
    (net (code "84") (name "/SLOTn.LVDS_14_N") (class "Default")
      (node (ref "J2") (pin "H1") (pinfunction "H1_H1") (pintype "bidirectional"))
    )
    (net (code "85") (name "/SLOTn.LVDS_14_P") (class "Default")
      (node (ref "J2") (pin "G1") (pinfunction "G1_G1") (pintype "bidirectional"))
    )
    (net (code "86") (name "/SLOTn.LVDS_15_N") (class "Default")
      (node (ref "R15") (pin "2") (pinfunction "2_2") (pintype "passive"))
      (node (ref "R16") (pin "1") (pinfunction "1_1") (pintype "passive"))
    )
    (net (code "87") (name "/SLOTn.LVDS_15_P") (class "Default")
      (node (ref "R13") (pin "2") (pinfunction "2_2") (pintype "passive"))
      (node (ref "R14") (pin "1") (pinfunction "1_1") (pintype "passive"))
    )
    (net (code "90") (name "EEM_JTAG_VCC") (class "Default")
      (node (ref "C29") (pin "2") (pinfunction "2_2") (pintype "passive"))
      (node (ref "C6") (pin "2") (pinfunction "2_2") (pintype "passive"))
      (node (ref "C7") (pin "2") (pinfunction "2_2") (pintype "passive"))
      (node (ref "IC15") (pin "6") (pinfunction "VCCB_6") (pintype "power_in"))
      (node (ref "IC4") (pin "6") (pinfunction "VCCB_6") (pintype "power_in"))
      (node (ref "IC5") (pin "6") (pinfunction "VCCB_6") (pintype "power_in"))
      (node (ref "J3") (pin "2") (pinfunction "2_2") (pintype "bidirectional"))
    )
    (net (code "91") (name "GND") (class "Default")
      (node (ref "C1") (pin "1") (pinfunction "1_1") (pintype "passive"))
      (node (ref "C10") (pin "1") (pinfunction "1_1") (pintype "passive"))
      (node (ref "C2") (pin "1") (pinfunction "1_1") (pintype "passive"))
      (node (ref "C28") (pin "1") (pinfunction "1_1") (pintype "passive"))
      (node (ref "C29") (pin "1") (pinfunction "1_1") (pintype "passive"))
      (node (ref "C3") (pin "1") (pinfunction "1_1") (pintype "passive"))
      (node (ref "C4") (pin "1") (pinfunction "1_1") (pintype "passive"))
      (node (ref "C5") (pin "1") (pinfunction "1_1") (pintype "passive"))
      (node (ref "C6") (pin "1") (pinfunction "1_1") (pintype "passive"))
      (node (ref "C7") (pin "1") (pinfunction "1_1") (pintype "passive"))
      (node (ref "C8") (pin "1") (pinfunction "1_1") (pintype "passive"))
      (node (ref "C9") (pin "1") (pinfunction "1_1") (pintype "passive"))
      (node (ref "D1") (pin "2") (pinfunction "A_2") (pintype "passive"))
      (node (ref "D1") (pin "3") (pinfunction "C_3") (pintype "passive"))
      (node (ref "D2") (pin "2") (pinfunction "A_2") (pintype "passive"))
      (node (ref "D3") (pin "2") (pinfunction "A_2") (pintype "passive"))
      (node (ref "D4") (pin "2") (pinfunction "A_2") (pintype "passive"))
      (node (ref "IC1") (pin "11") (pinfunction "GND_11") (pintype "power_in"))
      (node (ref "IC1") (pin "2") (pinfunction "OEn_2") (pintype "input"))
      (node (ref "IC1") (pin "20") (pinfunction "GND_20") (pintype "power_in"))
      (node (ref "IC1") (pin "21") (pinfunction "EP_21") (pintype "power_in"))
      (node (ref "IC1") (pin "5") (pinfunction "GND_5") (pintype "power_in"))
      (node (ref "IC15") (pin "3") (pinfunction "GND_3") (pintype "power_in"))
      (node (ref "IC15") (pin "9") (pinfunction "A2_9") (pintype "bidirectional"))
      (node (ref "IC2") (pin "11") (pinfunction "GND_11") (pintype "power_in"))
      (node (ref "IC2") (pin "2") (pinfunction "OEn_2") (pintype "input"))
      (node (ref "IC2") (pin "20") (pinfunction "GND_20") (pintype "power_in"))
      (node (ref "IC2") (pin "21") (pinfunction "EP_21") (pintype "power_in"))
      (node (ref "IC2") (pin "5") (pinfunction "GND_5") (pintype "power_in"))
      (node (ref "IC3") (pin "11") (pinfunction "GND_11") (pintype "power_in"))
      (node (ref "IC3") (pin "2") (pinfunction "OEn_2") (pintype "input"))
      (node (ref "IC3") (pin "20") (pinfunction "GND_20") (pintype "power_in"))
      (node (ref "IC3") (pin "21") (pinfunction "EP_21") (pintype "power_in"))
      (node (ref "IC3") (pin "5") (pinfunction "GND_5") (pintype "power_in"))
      (node (ref "IC4") (pin "3") (pinfunction "GND_3") (pintype "power_in"))
      (node (ref "IC5") (pin "10") (pinfunction "DIR1_10") (pintype "input"))
      (node (ref "IC5") (pin "3") (pinfunction "GND_3") (pintype "power_in"))
      (node (ref "IC6") (pin "12") (pinfunction "GND_12") (pintype "power_in"))
      (node (ref "IC6") (pin "9") (pinfunction "~{EN}_9") (pintype "input"))
      (node (ref "IC7") (pin "4") (pinfunction "GND_4") (pintype "power_in"))
      (node (ref "J1") (pin "A2") (pinfunction "A2_A2") (pintype "bidirectional"))
      (node (ref "J1") (pin "A4") (pinfunction "A4_A4") (pintype "bidirectional"))
      (node (ref "J1") (pin "A6") (pinfunction "A6_A6") (pintype "bidirectional"))
      (node (ref "J1") (pin "C1") (pinfunction "C1_C1") (pintype "bidirectional"))
      (node (ref "J1") (pin "C5") (pinfunction "C5_C5") (pintype "bidirectional"))
      (node (ref "J1") (pin "D2") (pinfunction "D2_D2") (pintype "bidirectional"))
      (node (ref "J1") (pin "D4") (pinfunction "D4_D4") (pintype "bidirectional"))
      (node (ref "J1") (pin "D6") (pinfunction "D6_D6") (pintype "bidirectional"))
      (node (ref "J1") (pin "F1") (pinfunction "F1_F1") (pintype "bidirectional"))
      (node (ref "J1") (pin "F5") (pinfunction "F5_F5") (pintype "bidirectional"))
      (node (ref "J1") (pin "G2") (pinfunction "G2_G2") (pintype "bidirectional"))
      (node (ref "J1") (pin "G4") (pinfunction "G4_G4") (pintype "bidirectional"))
      (node (ref "J1") (pin "G6") (pinfunction "G6_G6") (pintype "bidirectional"))
      (node (ref "J1") (pin "I1") (pinfunction "I1_I1") (pintype "bidirectional"))
      (node (ref "J1") (pin "I5") (pinfunction "I5_I5") (pintype "bidirectional"))
      (node (ref "J1") (pin "J2") (pinfunction "J2_J2") (pintype "bidirectional"))
      (node (ref "J1") (pin "J4") (pinfunction "J4_J4") (pintype "bidirectional"))
      (node (ref "J1") (pin "J6") (pinfunction "J6_J6") (pintype "bidirectional"))
      (node (ref "J1") (pin "L1") (pinfunction "L1_L1") (pintype "bidirectional"))
      (node (ref "J1") (pin "L5") (pinfunction "L5_L5") (pintype "bidirectional"))
      (node (ref "J2") (pin "A2") (pinfunction "A2_A2") (pintype "bidirectional"))
      (node (ref "J2") (pin "A4") (pinfunction "A4_A4") (pintype "bidirectional"))
      (node (ref "J2") (pin "A6") (pinfunction "A6_A6") (pintype "bidirectional"))
      (node (ref "J2") (pin "C1") (pinfunction "C1_C1") (pintype "bidirectional"))
      (node (ref "J2") (pin "C3") (pinfunction "C3_C3") (pintype "bidirectional"))
      (node (ref "J2") (pin "C5") (pinfunction "C5_C5") (pintype "bidirectional"))
      (node (ref "J2") (pin "C7") (pinfunction "C7_C7") (pintype "bidirectional"))
      (node (ref "J2") (pin "D2") (pinfunction "D2_D2") (pintype "bidirectional"))
      (node (ref "J2") (pin "D4") (pinfunction "D4_D4") (pintype "bidirectional"))
      (node (ref "J2") (pin "D6") (pinfunction "D6_D6") (pintype "bidirectional"))
      (node (ref "J2") (pin "F1") (pinfunction "F1_F1") (pintype "bidirectional"))
      (node (ref "J2") (pin "F3") (pinfunction "F3_F3") (pintype "bidirectional"))
      (node (ref "J2") (pin "F5") (pinfunction "F5_F5") (pintype "bidirectional"))
      (node (ref "J2") (pin "F7") (pinfunction "F7_F7") (pintype "bidirectional"))
      (node (ref "J2") (pin "G2") (pinfunction "G2_G2") (pintype "bidirectional"))
      (node (ref "J2") (pin "G4") (pinfunction "G4_G4") (pintype "bidirectional"))
      (node (ref "J2") (pin "G6") (pinfunction "G6_G6") (pintype "bidirectional"))
      (node (ref "J2") (pin "G8") (pinfunction "G8_G8") (pintype "bidirectional"))
      (node (ref "J2") (pin "I1") (pinfunction "I1_I1") (pintype "bidirectional"))
      (node (ref "J2") (pin "I3") (pinfunction "I3_I3") (pintype "bidirectional"))
      (node (ref "J2") (pin "I5") (pinfunction "I5_I5") (pintype "bidirectional"))
      (node (ref "J2") (pin "I7") (pinfunction "I7_I7") (pintype "bidirectional"))
      (node (ref "J2") (pin "J2") (pinfunction "J2_J2") (pintype "bidirectional"))
      (node (ref "J2") (pin "J4") (pinfunction "J4_J4") (pintype "bidirectional"))
      (node (ref "J2") (pin "J6") (pinfunction "J6_J6") (pintype "bidirectional"))
      (node (ref "J2") (pin "J8") (pinfunction "J8_J8") (pintype "bidirectional"))
      (node (ref "J2") (pin "L1") (pinfunction "L1_L1") (pintype "bidirectional"))
      (node (ref "J2") (pin "L3") (pinfunction "L3_L3") (pintype "bidirectional"))
      (node (ref "J2") (pin "L5") (pinfunction "L5_L5") (pintype "bidirectional"))
      (node (ref "J2") (pin "L7") (pinfunction "L7_L7") (pintype "bidirectional"))
      (node (ref "J3") (pin "1") (pinfunction "1_1") (pintype "bidirectional"))
      (node (ref "J3") (pin "11") (pinfunction "11_11") (pintype "bidirectional"))
      (node (ref "J3") (pin "13") (pinfunction "13_13") (pintype "bidirectional"))
      (node (ref "J3") (pin "3") (pinfunction "3_3") (pintype "bidirectional"))
      (node (ref "J3") (pin "5") (pinfunction "5_5") (pintype "bidirectional"))
      (node (ref "J3") (pin "7") (pinfunction "7_7") (pintype "bidirectional"))
      (node (ref "J3") (pin "9") (pinfunction "9_9") (pintype "bidirectional"))
      (node (ref "R12") (pin "1") (pinfunction "1_1") (pintype "passive"))
      (node (ref "R53") (pin "1") (pinfunction "1_1") (pintype "passive"))
      (node (ref "T1") (pin "2") (pinfunction "S_2") (pintype "passive"))
    )
    (net (code "92") (name "Net-(D1A-C)") (class "Default")
      (node (ref "D1") (pin "1") (pinfunction "C_1") (pintype "passive"))
      (node (ref "J1") (pin "H2") (pinfunction "H2_H2") (pintype "bidirectional"))
      (node (ref "R4") (pin "2") (pinfunction "2_2") (pintype "passive"))
    )
    (net (code "93") (name "Net-(D1D-C)") (class "Default")
      (node (ref "D1") (pin "5") (pinfunction "C_5") (pintype "passive"))
      (node (ref "J1") (pin "K2") (pinfunction "K2_K2") (pintype "bidirectional"))
      (node (ref "R9") (pin "2") (pinfunction "2_2") (pintype "passive"))
    )
    (net (code "94") (name "Net-(D2A-C)") (class "Default")
      (node (ref "D2") (pin "1") (pinfunction "C_1") (pintype "passive"))
      (node (ref "J1") (pin "I2") (pinfunction "I2_I2") (pintype "bidirectional"))
      (node (ref "R6") (pin "2") (pinfunction "2_2") (pintype "passive"))
    )
    (net (code "95") (name "Net-(D2B-C)") (class "Default")
      (node (ref "D2") (pin "3") (pinfunction "C_3") (pintype "passive"))
      (node (ref "J1") (pin "G3") (pinfunction "G3_G3") (pintype "bidirectional"))
      (node (ref "R3") (pin "2") (pinfunction "2_2") (pintype "passive"))
    )
    (net (code "96") (name "Net-(D2C-C)") (class "Default")
      (node (ref "D2") (pin "4") (pinfunction "C_4") (pintype "passive"))
      (node (ref "J1") (pin "K3") (pinfunction "K3_K3") (pintype "bidirectional"))
      (node (ref "R10") (pin "2") (pinfunction "2_2") (pintype "passive"))
    )
    (net (code "97") (name "Net-(D2D-C)") (class "Default")
      (node (ref "D2") (pin "5") (pinfunction "C_5") (pintype "passive"))
      (node (ref "J1") (pin "J3") (pinfunction "J3_J3") (pintype "bidirectional"))
      (node (ref "R8") (pin "2") (pinfunction "2_2") (pintype "passive"))
    )
    (net (code "98") (name "Net-(D2E-C)") (class "Default")
      (node (ref "D2") (pin "6") (pinfunction "C_6") (pintype "passive"))
      (node (ref "J1") (pin "H3") (pinfunction "H3_H3") (pintype "bidirectional"))
      (node (ref "R5") (pin "2") (pinfunction "2_2") (pintype "passive"))
    )
    (net (code "99") (name "Net-(D3A-C)") (class "Default")
      (node (ref "D3") (pin "1") (pinfunction "C_1") (pintype "passive"))
      (node (ref "J1") (pin "L3") (pinfunction "L3_L3") (pintype "bidirectional"))
      (node (ref "R11") (pin "2") (pinfunction "2_2") (pintype "passive"))
    )
    (net (code "100") (name "Net-(D3B-C)") (class "Default")
      (node (ref "D3") (pin "3") (pinfunction "C_3") (pintype "passive"))
      (node (ref "J1") (pin "I3") (pinfunction "I3_I3") (pintype "bidirectional"))
      (node (ref "R7") (pin "2") (pinfunction "2_2") (pintype "passive"))
    )
    (net (code "101") (name "Net-(D3C-C)") (class "Default")
      (node (ref "D3") (pin "4") (pinfunction "C_4") (pintype "passive"))
      (node (ref "J1") (pin "C3") (pinfunction "C3_C3") (pintype "bidirectional"))
      (node (ref "R1") (pin "2") (pinfunction "2_2") (pintype "passive"))
    )
    (net (code "102") (name "Net-(D3E-C)") (class "Default")
      (node (ref "D3") (pin "6") (pinfunction "C_6") (pintype "passive"))
      (node (ref "J1") (pin "F3") (pinfunction "F3_F3") (pintype "bidirectional"))
      (node (ref "R2") (pin "2") (pinfunction "2_2") (pintype "passive"))
    )
    (net (code "103") (name "Net-(IC15-B1)") (class "Default")
      (node (ref "IC15") (pin "5") (pinfunction "B1_5") (pintype "bidirectional"))
      (node (ref "R54") (pin "1") (pinfunction "1_1") (pintype "passive"))
      (node (ref "R55") (pin "1") (pinfunction "1_1") (pintype "passive"))
    )
    (net (code "104") (name "P3V3_MP") (class "Default")
      (node (ref "C1") (pin "2") (pinfunction "2_2") (pintype "passive"))
      (node (ref "C10") (pin "2") (pinfunction "2_2") (pintype "passive"))
      (node (ref "C2") (pin "2") (pinfunction "2_2") (pintype "passive"))
      (node (ref "C28") (pin "2") (pinfunction "2_2") (pintype "passive"))
      (node (ref "C3") (pin "2") (pinfunction "2_2") (pintype "passive"))
      (node (ref "C4") (pin "2") (pinfunction "2_2") (pintype "passive"))
      (node (ref "C5") (pin "2") (pinfunction "2_2") (pintype "passive"))
      (node (ref "C8") (pin "2") (pinfunction "2_2") (pintype "passive"))
      (node (ref "C9") (pin "2") (pinfunction "2_2") (pintype "passive"))
      (node (ref "IC1") (pin "6") (pinfunction "VDD_6") (pintype "power_in"))
      (node (ref "IC15") (pin "1") (pinfunction "DIR2_1") (pintype "input"))
      (node (ref "IC15") (pin "10") (pinfunction "DIR1_10") (pintype "input"))
      (node (ref "IC15") (pin "7") (pinfunction "VCCA_7") (pintype "power_in"))
      (node (ref "IC2") (pin "6") (pinfunction "VDD_6") (pintype "power_in"))
      (node (ref "IC3") (pin "6") (pinfunction "VDD_6") (pintype "power_in"))
      (node (ref "IC4") (pin "1") (pinfunction "DIR2_1") (pintype "input"))
      (node (ref "IC4") (pin "10") (pinfunction "DIR1_10") (pintype "input"))
      (node (ref "IC4") (pin "7") (pinfunction "VCCA_7") (pintype "power_in"))
      (node (ref "IC5") (pin "1") (pinfunction "DIR2_1") (pintype "input"))
      (node (ref "IC5") (pin "7") (pinfunction "VCCA_7") (pintype "power_in"))
      (node (ref "IC6") (pin "13") (pinfunction "VCC_13") (pintype "power_in"))
      (node (ref "IC7") (pin "1") (pinfunction "VCC_1") (pintype "power_in"))
      (node (ref "R17") (pin "2") (pinfunction "2_2") (pintype "passive"))
      (node (ref "R18") (pin "2") (pinfunction "2_2") (pintype "passive"))
      (node (ref "R19") (pin "2") (pinfunction "2_2") (pintype "passive"))
      (node (ref "R20") (pin "2") (pinfunction "2_2") (pintype "passive"))
      (node (ref "R21") (pin "2") (pinfunction "2_2") (pintype "passive"))
      (node (ref "R22") (pin "2") (pinfunction "2_2") (pintype "passive"))
    )
    (net (code "105") (name "P5V0_MP") (class "Default")
      (node (ref "J1") (pin "B1") (pinfunction "B1_B1") (pintype "bidirectional"))
    )
    (net (code "106") (name "P12V0") (class "Default")
      (node (ref "J1") (pin "A1") (pinfunction "A1_A1") (pintype "bidirectional"))
      (node (ref "J1") (pin "D1") (pinfunction "D1_D1") (pintype "bidirectional"))
      (node (ref "J1") (pin "E1") (pinfunction "E1_E1") (pintype "bidirectional"))
      (node (ref "J1") (pin "G1") (pinfunction "G1_G1") (pintype "bidirectional"))
      (node (ref "J1") (pin "H1") (pinfunction "H1_H1") (pintype "bidirectional"))
      (node (ref "J1") (pin "J1") (pinfunction "J1_J1") (pintype "bidirectional"))
      (node (ref "J1") (pin "K1") (pinfunction "K1_K1") (pintype "bidirectional"))
    )
    (net (code "107") (name "unconnected-(D3D-C-Pad5)") (class "Default")
      (node (ref "D3") (pin "5") (pinfunction "C_5") (pintype "passive+no_connect"))
    )
    (net (code "108") (name "unconnected-(IC1-RSVD1-Pad1)") (class "Default")
      (node (ref "IC1") (pin "1") (pinfunction "RSVD1_1") (pintype "power_in+no_connect"))
    )
    (net (code "109") (name "unconnected-(IC1-RSVD2-Pad10)") (class "Default")
      (node (ref "IC1") (pin "10") (pinfunction "RSVD2_10") (pintype "power_in+no_connect"))
    )
    (net (code "110") (name "unconnected-(IC2-RSVD1-Pad1)") (class "Default")
      (node (ref "IC2") (pin "1") (pinfunction "RSVD1_1") (pintype "power_in+no_connect"))
    )
    (net (code "111") (name "unconnected-(IC2-RSVD2-Pad10)") (class "Default")
      (node (ref "IC2") (pin "10") (pinfunction "RSVD2_10") (pintype "power_in+no_connect"))
    )
    (net (code "112") (name "unconnected-(IC3-A1+-Pad7)") (class "Default")
      (node (ref "IC3") (pin "7") (pinfunction "A1+_7") (pintype "bidirectional+no_connect"))
    )
    (net (code "113") (name "unconnected-(IC3-A1--Pad8)") (class "Default")
      (node (ref "IC3") (pin "8") (pinfunction "A1-_8") (pintype "bidirectional+no_connect"))
    )
    (net (code "114") (name "unconnected-(IC3-B1+-Pad17)") (class "Default")
      (node (ref "IC3") (pin "17") (pinfunction "B1+_17") (pintype "bidirectional+no_connect"))
    )
    (net (code "115") (name "unconnected-(IC3-B1--Pad16)") (class "Default")
      (node (ref "IC3") (pin "16") (pinfunction "B1-_16") (pintype "bidirectional+no_connect"))
    )
    (net (code "116") (name "unconnected-(IC3-C1+-Pad13)") (class "Default")
      (node (ref "IC3") (pin "13") (pinfunction "C1+_13") (pintype "bidirectional+no_connect"))
    )
    (net (code "117") (name "unconnected-(IC3-C1--Pad12)") (class "Default")
      (node (ref "IC3") (pin "12") (pinfunction "C1-_12") (pintype "bidirectional+no_connect"))
    )
    (net (code "118") (name "unconnected-(IC3-RSVD1-Pad1)") (class "Default")
      (node (ref "IC3") (pin "1") (pinfunction "RSVD1_1") (pintype "power_in+no_connect"))
    )
    (net (code "119") (name "unconnected-(IC3-RSVD2-Pad10)") (class "Default")
      (node (ref "IC3") (pin "10") (pinfunction "RSVD2_10") (pintype "power_in+no_connect"))
    )
    (net (code "120") (name "unconnected-(IC7-NC-Pad3)") (class "Default")
      (node (ref "IC7") (pin "3") (pinfunction "NC_3") (pintype "passive"))
    )
    (net (code "121") (name "unconnected-(IC7-NC-Pad5)") (class "Default")
      (node (ref "IC7") (pin "5") (pinfunction "NC_5") (pintype "passive"))
    )
    (net (code "122") (name "unconnected-(IC7-NC-Pad6)") (class "Default")
      (node (ref "IC7") (pin "6") (pinfunction "NC_6") (pintype "passive"))
    )
    (net (code "123") (name "unconnected-(IC15-B2-Pad4)") (class "Default")
      (node (ref "IC15") (pin "4") (pinfunction "B2_4") (pintype "bidirectional"))
    )
    (net (code "124") (name "unconnected-(J1-PadA5)") (class "Default")
      (node (ref "J1") (pin "A5") (pinfunction "A5_A5") (pintype "bidirectional+no_connect"))
    )
    (net (code "125") (name "unconnected-(J1-PadB5)") (class "Default")
      (node (ref "J1") (pin "B5") (pinfunction "B5_B5") (pintype "bidirectional+no_connect"))
    )
    (net (code "126") (name "unconnected-(J1-PadL2)") (class "Default")
      (node (ref "J1") (pin "L2") (pinfunction "L2_L2") (pintype "bidirectional+no_connect"))
    )
    (net (code "127") (name "unconnected-(J2-PadA3)") (class "Default")
      (node (ref "J2") (pin "A3") (pinfunction "A3_A3") (pintype "bidirectional+no_connect"))
    )
    (net (code "128") (name "unconnected-(J2-PadA5)") (class "Default")
      (node (ref "J2") (pin "A5") (pinfunction "A5_A5") (pintype "bidirectional+no_connect"))
    )
    (net (code "129") (name "unconnected-(J2-PadA7)") (class "Default")
      (node (ref "J2") (pin "A7") (pinfunction "A7_A7") (pintype "bidirectional+no_connect"))
    )
    (net (code "130") (name "unconnected-(J2-PadA8)") (class "Default")
      (node (ref "J2") (pin "A8") (pinfunction "A8_A8") (pintype "bidirectional+no_connect"))
    )
    (net (code "131") (name "unconnected-(J2-PadB2)") (class "Default")
      (node (ref "J2") (pin "B2") (pinfunction "B2_B2") (pintype "bidirectional+no_connect"))
    )
    (net (code "132") (name "unconnected-(J2-PadB3)") (class "Default")
      (node (ref "J2") (pin "B3") (pinfunction "B3_B3") (pintype "bidirectional+no_connect"))
    )
    (net (code "133") (name "unconnected-(J2-PadB4)") (class "Default")
      (node (ref "J2") (pin "B4") (pinfunction "B4_B4") (pintype "bidirectional+no_connect"))
    )
    (net (code "134") (name "unconnected-(J2-PadB5)") (class "Default")
      (node (ref "J2") (pin "B5") (pinfunction "B5_B5") (pintype "bidirectional+no_connect"))
    )
    (net (code "135") (name "unconnected-(J2-PadB6)") (class "Default")
      (node (ref "J2") (pin "B6") (pinfunction "B6_B6") (pintype "bidirectional+no_connect"))
    )
    (net (code "136") (name "unconnected-(J2-PadB7)") (class "Default")
      (node (ref "J2") (pin "B7") (pinfunction "B7_B7") (pintype "bidirectional+no_connect"))
    )
    (net (code "137") (name "unconnected-(J2-PadB8)") (class "Default")
      (node (ref "J2") (pin "B8") (pinfunction "B8_B8") (pintype "bidirectional+no_connect"))
    )
    (net (code "138") (name "unconnected-(J2-PadC2)") (class "Default")
      (node (ref "J2") (pin "C2") (pinfunction "C2_C2") (pintype "bidirectional+no_connect"))
    )
    (net (code "139") (name "unconnected-(J2-PadC4)") (class "Default")
      (node (ref "J2") (pin "C4") (pinfunction "C4_C4") (pintype "bidirectional+no_connect"))
    )
    (net (code "140") (name "unconnected-(J2-PadC6)") (class "Default")
      (node (ref "J2") (pin "C6") (pinfunction "C6_C6") (pintype "bidirectional+no_connect"))
    )
    (net (code "141") (name "unconnected-(J2-PadC8)") (class "Default")
      (node (ref "J2") (pin "C8") (pinfunction "C8_C8") (pintype "bidirectional+no_connect"))
    )
    (net (code "142") (name "unconnected-(J2-PadD3)") (class "Default")
      (node (ref "J2") (pin "D3") (pinfunction "D3_D3") (pintype "bidirectional+no_connect"))
    )
    (net (code "143") (name "unconnected-(J2-PadD5)") (class "Default")
      (node (ref "J2") (pin "D5") (pinfunction "D5_D5") (pintype "bidirectional+no_connect"))
    )
    (net (code "144") (name "unconnected-(J2-PadD7)") (class "Default")
      (node (ref "J2") (pin "D7") (pinfunction "D7_D7") (pintype "bidirectional+no_connect"))
    )
    (net (code "145") (name "unconnected-(J2-PadD8)") (class "Default")
      (node (ref "J2") (pin "D8") (pinfunction "D8_D8") (pintype "bidirectional+no_connect"))
    )
    (net (code "146") (name "unconnected-(J2-PadE2)") (class "Default")
      (node (ref "J2") (pin "E2") (pinfunction "E2_E2") (pintype "bidirectional+no_connect"))
    )
    (net (code "147") (name "unconnected-(J2-PadE3)") (class "Default")
      (node (ref "J2") (pin "E3") (pinfunction "E3_E3") (pintype "bidirectional+no_connect"))
    )
    (net (code "148") (name "unconnected-(J2-PadE4)") (class "Default")
      (node (ref "J2") (pin "E4") (pinfunction "E4_E4") (pintype "bidirectional+no_connect"))
    )
    (net (code "149") (name "unconnected-(J2-PadE5)") (class "Default")
      (node (ref "J2") (pin "E5") (pinfunction "E5_E5") (pintype "bidirectional+no_connect"))
    )
    (net (code "150") (name "unconnected-(J2-PadE6)") (class "Default")
      (node (ref "J2") (pin "E6") (pinfunction "E6_E6") (pintype "bidirectional+no_connect"))
    )
    (net (code "151") (name "unconnected-(J2-PadE7)") (class "Default")
      (node (ref "J2") (pin "E7") (pinfunction "E7_E7") (pintype "bidirectional+no_connect"))
    )
    (net (code "152") (name "unconnected-(J2-PadE8)") (class "Default")
      (node (ref "J2") (pin "E8") (pinfunction "E8_E8") (pintype "bidirectional+no_connect"))
    )
    (net (code "153") (name "unconnected-(J2-PadF2)") (class "Default")
      (node (ref "J2") (pin "F2") (pinfunction "F2_F2") (pintype "bidirectional+no_connect"))
    )
    (net (code "154") (name "unconnected-(J2-PadF4)") (class "Default")
      (node (ref "J2") (pin "F4") (pinfunction "F4_F4") (pintype "bidirectional+no_connect"))
    )
    (net (code "155") (name "unconnected-(J2-PadF6)") (class "Default")
      (node (ref "J2") (pin "F6") (pinfunction "F6_F6") (pintype "bidirectional+no_connect"))
    )
    (net (code "156") (name "unconnected-(J2-PadF8)") (class "Default")
      (node (ref "J2") (pin "F8") (pinfunction "F8_F8") (pintype "bidirectional+no_connect"))
    )
    (net (code "157") (name "unconnected-(J2-PadG3)") (class "Default")
      (node (ref "J2") (pin "G3") (pinfunction "G3_G3") (pintype "bidirectional+no_connect"))
    )
    (net (code "158") (name "unconnected-(J2-PadG5)") (class "Default")
      (node (ref "J2") (pin "G5") (pinfunction "G5_G5") (pintype "bidirectional+no_connect"))
    )
    (net (code "159") (name "unconnected-(J2-PadG7)") (class "Default")
      (node (ref "J2") (pin "G7") (pinfunction "G7_G7") (pintype "bidirectional+no_connect"))
    )
    (net (code "160") (name "unconnected-(J2-PadH2)") (class "Default")
      (node (ref "J2") (pin "H2") (pinfunction "H2_H2") (pintype "bidirectional+no_connect"))
    )
    (net (code "161") (name "unconnected-(J2-PadH3)") (class "Default")
      (node (ref "J2") (pin "H3") (pinfunction "H3_H3") (pintype "bidirectional+no_connect"))
    )
    (net (code "162") (name "unconnected-(J2-PadH4)") (class "Default")
      (node (ref "J2") (pin "H4") (pinfunction "H4_H4") (pintype "bidirectional+no_connect"))
    )
    (net (code "163") (name "unconnected-(J2-PadH5)") (class "Default")
      (node (ref "J2") (pin "H5") (pinfunction "H5_H5") (pintype "bidirectional+no_connect"))
    )
    (net (code "164") (name "unconnected-(J2-PadH6)") (class "Default")
      (node (ref "J2") (pin "H6") (pinfunction "H6_H6") (pintype "bidirectional+no_connect"))
    )
    (net (code "165") (name "unconnected-(J2-PadH7)") (class "Default")
      (node (ref "J2") (pin "H7") (pinfunction "H7_H7") (pintype "bidirectional+no_connect"))
    )
    (net (code "166") (name "unconnected-(J2-PadH8)") (class "Default")
      (node (ref "J2") (pin "H8") (pinfunction "H8_H8") (pintype "bidirectional+no_connect"))
    )
    (net (code "167") (name "unconnected-(J2-PadI2)") (class "Default")
      (node (ref "J2") (pin "I2") (pinfunction "I2_I2") (pintype "bidirectional+no_connect"))
    )
    (net (code "168") (name "unconnected-(J2-PadI4)") (class "Default")
      (node (ref "J2") (pin "I4") (pinfunction "I4_I4") (pintype "bidirectional+no_connect"))
    )
    (net (code "169") (name "unconnected-(J2-PadI6)") (class "Default")
      (node (ref "J2") (pin "I6") (pinfunction "I6_I6") (pintype "bidirectional+no_connect"))
    )
    (net (code "170") (name "unconnected-(J2-PadI8)") (class "Default")
      (node (ref "J2") (pin "I8") (pinfunction "I8_I8") (pintype "bidirectional+no_connect"))
    )
    (net (code "171") (name "unconnected-(J2-PadJ3)") (class "Default")
      (node (ref "J2") (pin "J3") (pinfunction "J3_J3") (pintype "bidirectional+no_connect"))
    )
    (net (code "172") (name "unconnected-(J2-PadJ5)") (class "Default")
      (node (ref "J2") (pin "J5") (pinfunction "J5_J5") (pintype "bidirectional+no_connect"))
    )
    (net (code "173") (name "unconnected-(J2-PadJ7)") (class "Default")
      (node (ref "J2") (pin "J7") (pinfunction "J7_J7") (pintype "bidirectional+no_connect"))
    )
    (net (code "174") (name "unconnected-(J2-PadK2)") (class "Default")
      (node (ref "J2") (pin "K2") (pinfunction "K2_K2") (pintype "bidirectional+no_connect"))
    )
    (net (code "175") (name "unconnected-(J2-PadK3)") (class "Default")
      (node (ref "J2") (pin "K3") (pinfunction "K3_K3") (pintype "bidirectional+no_connect"))
    )
    (net (code "176") (name "unconnected-(J2-PadK4)") (class "Default")
      (node (ref "J2") (pin "K4") (pinfunction "K4_K4") (pintype "bidirectional+no_connect"))
    )
    (net (code "177") (name "unconnected-(J2-PadK5)") (class "Default")
      (node (ref "J2") (pin "K5") (pinfunction "K5_K5") (pintype "bidirectional+no_connect"))
    )
    (net (code "178") (name "unconnected-(J2-PadK6)") (class "Default")
      (node (ref "J2") (pin "K6") (pinfunction "K6_K6") (pintype "bidirectional+no_connect"))
    )
    (net (code "179") (name "unconnected-(J2-PadK7)") (class "Default")
      (node (ref "J2") (pin "K7") (pinfunction "K7_K7") (pintype "bidirectional+no_connect"))
    )
    (net (code "180") (name "unconnected-(J2-PadK8)") (class "Default")
      (node (ref "J2") (pin "K8") (pinfunction "K8_K8") (pintype "bidirectional+no_connect"))
    )
    (net (code "181") (name "unconnected-(J2-PadL2)") (class "Default")
      (node (ref "J2") (pin "L2") (pinfunction "L2_L2") (pintype "bidirectional+no_connect"))
    )
    (net (code "182") (name "unconnected-(J2-PadL4)") (class "Default")
      (node (ref "J2") (pin "L4") (pinfunction "L4_L4") (pintype "bidirectional+no_connect"))
    )
    (net (code "183") (name "unconnected-(J2-PadL6)") (class "Default")
      (node (ref "J2") (pin "L6") (pinfunction "L6_L6") (pintype "bidirectional+no_connect"))
    )
    (net (code "184") (name "unconnected-(J2-PadL8)") (class "Default")
      (node (ref "J2") (pin "L8") (pinfunction "L8_L8") (pintype "bidirectional+no_connect"))
    )
    (net (code "185") (name "unconnected-(J3-Pad12)") (class "Default")
      (node (ref "J3") (pin "12") (pinfunction "12_12") (pintype "bidirectional+no_connect"))
    )
  )
)
